# RCboat.net
KiCad netlist of a schematic drawn in EAGLE
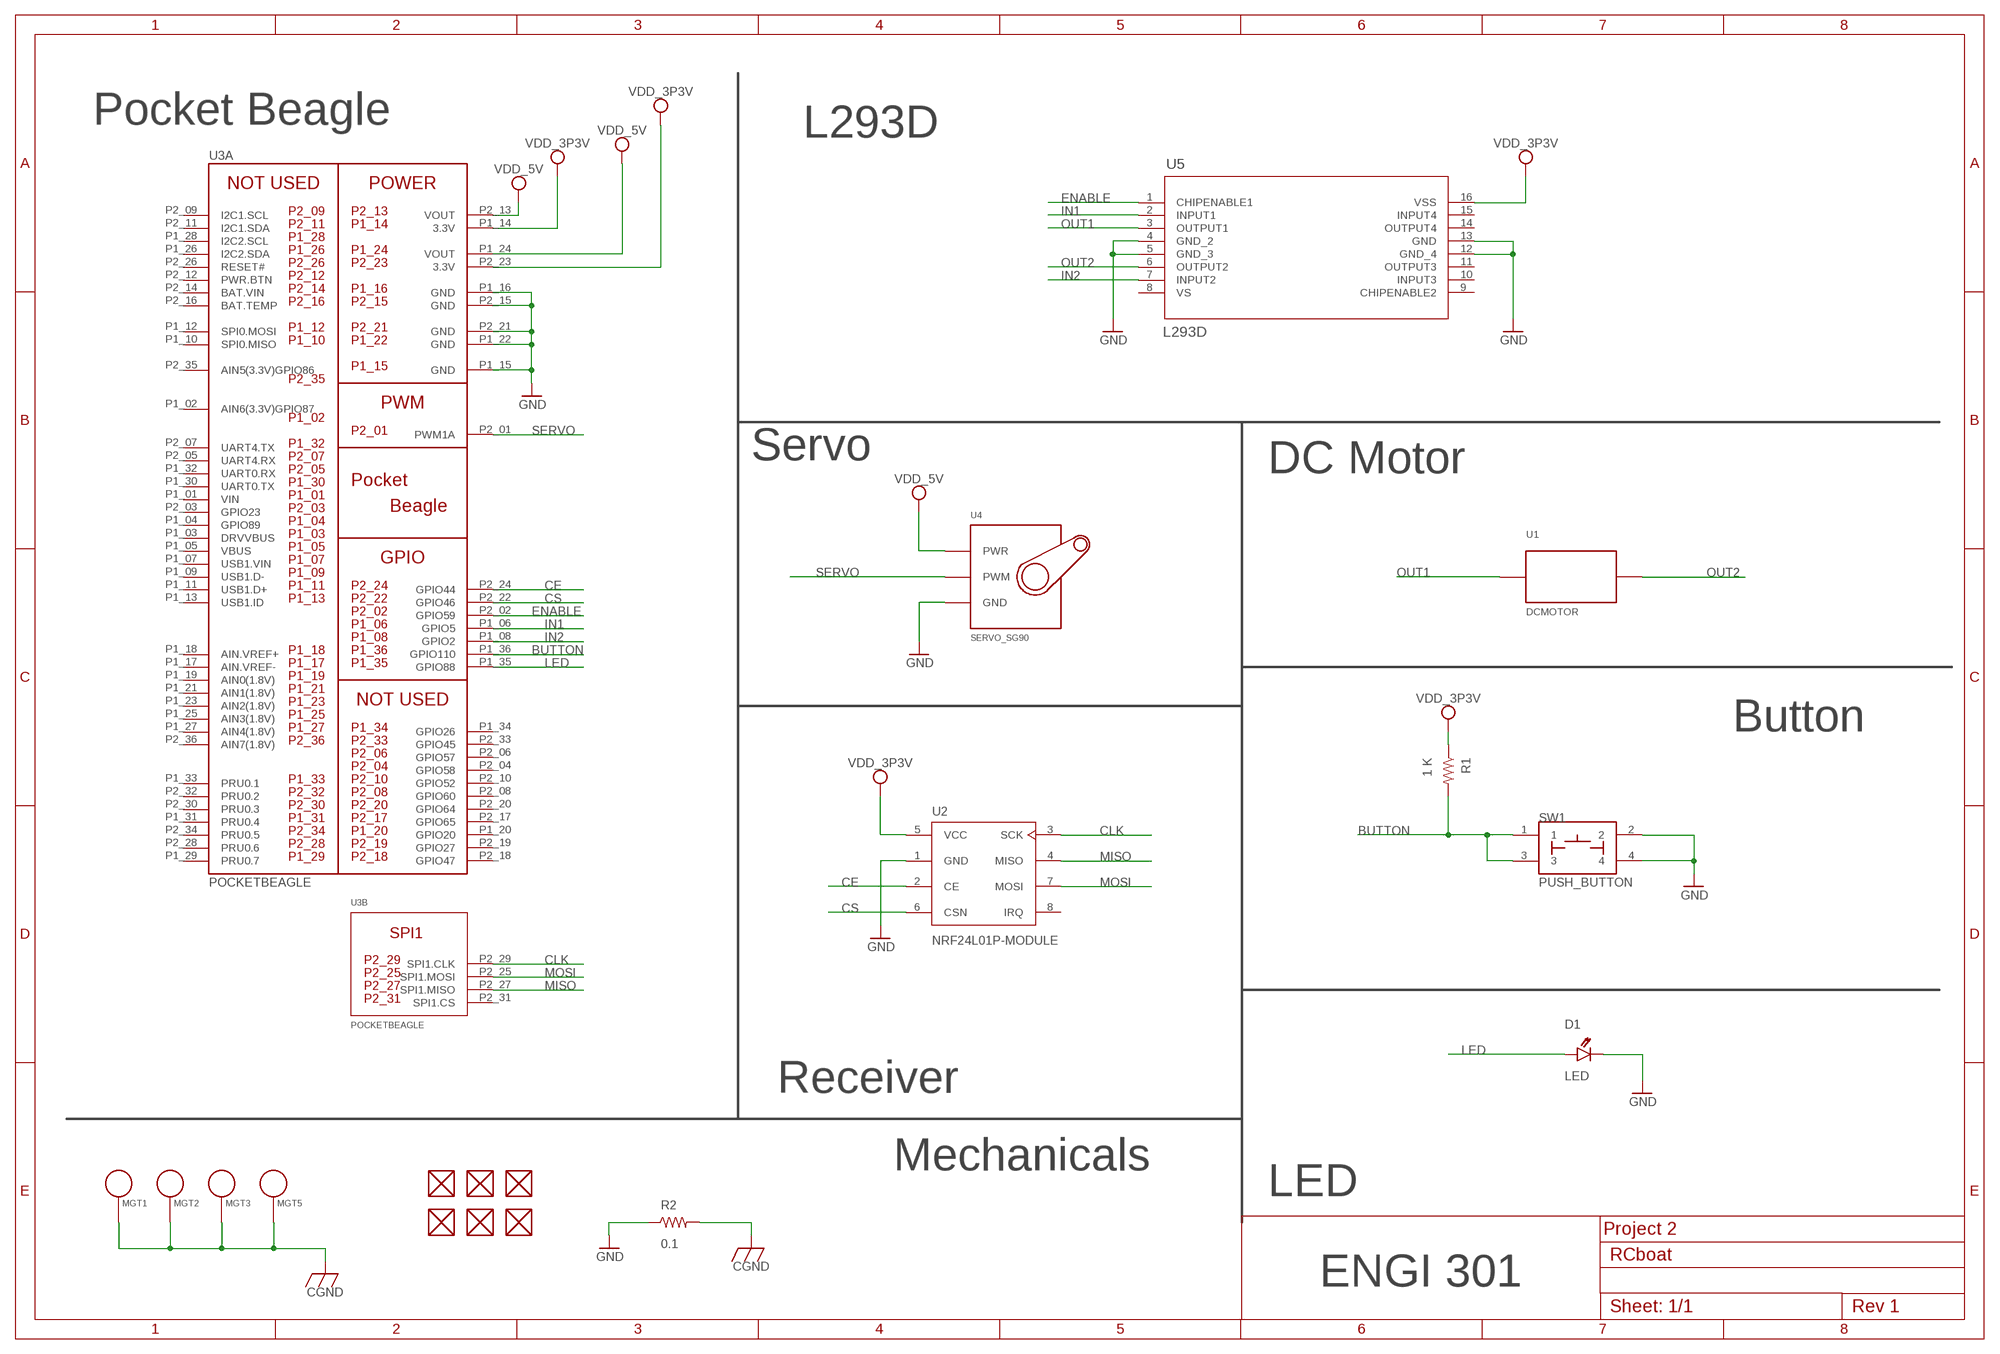
[diagram p0: schematic, sheet 1]

(export (version "E")
  (design (tool "Eeschema 10.0.6"))
  (components
    (comp (ref "D1")
      (value "LED")
      (footprint "eagle-import:EIA-STD")
      (libsource (lib "eagle-import") (part "LED"))
    )
    (comp (ref "FUD1")
      (value "FIDUCIAL")
      (footprint "eagle-import:FIDUCIAL_40MIL")
      (libsource (lib "eagle-import") (part "FIDUCIAL"))
    )
    (comp (ref "FUD2")
      (value "FIDUCIAL")
      (footprint "eagle-import:FIDUCIAL_40MIL")
      (libsource (lib "eagle-import") (part "FIDUCIAL"))
    )
    (comp (ref "FUD3")
      (value "FIDUCIAL")
      (footprint "eagle-import:FIDUCIAL_40MIL")
      (libsource (lib "eagle-import") (part "FIDUCIAL"))
    )
    (comp (ref "FUD4")
      (value "FIDUCIAL")
      (footprint "eagle-import:FIDUCIAL_40MIL")
      (libsource (lib "eagle-import") (part "FIDUCIAL"))
    )
    (comp (ref "FUD5")
      (value "FIDUCIAL")
      (footprint "eagle-import:FIDUCIAL_40MIL")
      (libsource (lib "eagle-import") (part "FIDUCIAL"))
    )
    (comp (ref "FUD6")
      (value "FIDUCIAL")
      (footprint "eagle-import:FIDUCIAL_40MIL")
      (libsource (lib "eagle-import") (part "FIDUCIAL"))
    )
    (comp (ref "MGT1")
      (value "MOUNTING_HOLE")
      (footprint "eagle-import:MOUNTING_HOLE")
      (libsource (lib "eagle-import") (part "MOUNTING_HOLE"))
    )
    (comp (ref "MGT2")
      (value "MOUNTING_HOLE")
      (footprint "eagle-import:MOUNTING_HOLE")
      (libsource (lib "eagle-import") (part "MOUNTING_HOLE"))
    )
    (comp (ref "MGT3")
      (value "MOUNTING_HOLE")
      (footprint "eagle-import:MOUNTING_HOLE")
      (libsource (lib "eagle-import") (part "MOUNTING_HOLE"))
    )
    (comp (ref "MGT5")
      (value "MOUNTING_HOLE")
      (footprint "eagle-import:MOUNTING_HOLE")
      (libsource (lib "eagle-import") (part "MOUNTING_HOLE"))
    )
    (comp (ref "R1")
      (value "1 K")
      (footprint "eagle-import:R0603")
      (libsource (lib "eagle-import") (part "R_R0603"))
    )
    (comp (ref "R2")
      (value "0.1")
      (footprint "eagle-import:R0805")
      (libsource (lib "eagle-import") (part "R_R0805"))
    )
    (comp (ref "SW1")
      (value "PUSH_BUTTON")
      (footprint "eagle-import:BUTTON_12.5MM")
      (libsource (lib "eagle-import") (part "PUSH_BUTTON"))
    )
    (comp (ref "U1")
      (value "DCMOTOR")
      (footprint "eagle-import:DCMOTOR")
      (libsource (lib "eagle-import") (part "DCMOTOR"))
    )
    (comp (ref "U2")
      (value "NRF24L01P-MODULE")
      (footprint "eagle-import:NRF24L01P-MODULE")
      (libsource (lib "eagle-import") (part "NRF24L01P-MODULE"))
    )
    (comp (ref "U3")
      (value "POCKETBEAGLE")
      (footprint "eagle-import:POCKETBEAGLE")
      (libsource (lib "eagle-import") (part "POCKETBEAGLE"))
    )
    (comp (ref "U4")
      (value "SERVO_SG90")
      (footprint "eagle-import:SERVO-X1")
      (libsource (lib "eagle-import") (part "SERVO_SG90"))
    )
    (comp (ref "U5")
      (value "L293D")
      (footprint "eagle-import:POWERDIP-16_STM")
      (fields (field (name "COPYRIGHT") "Copyright (C) 2021 Ultra Librarian. All rights reserved."))
      (libsource (lib "eagle-import") (part "L293D"))
    )
  )
  (nets
    (net (code "1") (name "/BAT.VIN") (class "Default")
      (node (ref "U3") (pin "P2_14") (pinfunction "BAT.VIN_P2_14") (pintype "power_in"))
    )
    (net (code "2") (name "/BUTTON") (class "Default")
      (node (ref "R1") (pin "2") (pinfunction "2_2") (pintype "passive"))
      (node (ref "SW1") (pin "1") (pinfunction "1_1") (pintype "bidirectional"))
      (node (ref "SW1") (pin "3") (pinfunction "3_3") (pintype "bidirectional"))
      (node (ref "U3") (pin "P1_36") (pinfunction "GPIO110_P1_36") (pintype "bidirectional"))
    )
    (net (code "3") (name "/CE") (class "Default")
      (node (ref "U2") (pin "2") (pinfunction "CE_2") (pintype "input"))
      (node (ref "U3") (pin "P2_24") (pinfunction "GPIO44_P2_24") (pintype "bidirectional"))
    )
    (net (code "4") (name "/CLK") (class "Default")
      (node (ref "U2") (pin "3") (pinfunction "SCK_3") (pintype "input"))
      (node (ref "U3") (pin "P2_29") (pinfunction "SPI1.CLK_P2_29") (pintype "bidirectional"))
    )
    (net (code "5") (name "/CS") (class "Default")
      (node (ref "U2") (pin "6") (pinfunction "CSN_6") (pintype "input"))
      (node (ref "U3") (pin "P2_22") (pinfunction "GPIO46_P2_22") (pintype "bidirectional"))
    )
    (net (code "6") (name "/ENABLE") (class "Default")
      (node (ref "U3") (pin "P2_02") (pinfunction "GPIO59_P2_02") (pintype "bidirectional"))
      (node (ref "U5") (pin "1") (pinfunction "CHIPENABLE1_1") (pintype "output"))
    )
    (net (code "7") (name "/IN1") (class "Default")
      (node (ref "U3") (pin "P1_06") (pinfunction "GPIO5_P1_06") (pintype "bidirectional"))
      (node (ref "U5") (pin "2") (pinfunction "INPUT1_2") (pintype "input"))
    )
    (net (code "8") (name "/IN2") (class "Default")
      (node (ref "U3") (pin "P1_08") (pinfunction "GPIO2_P1_08") (pintype "bidirectional"))
      (node (ref "U5") (pin "7") (pinfunction "INPUT2_7") (pintype "input"))
    )
    (net (code "9") (name "/LED") (class "Default")
      (node (ref "D1") (pin "ANODE") (pinfunction "ANODE_ANODE") (pintype "bidirectional"))
      (node (ref "U3") (pin "P1_35") (pinfunction "GPIO88_P1_35") (pintype "bidirectional"))
    )
    (net (code "10") (name "/MISO") (class "Default")
      (node (ref "U2") (pin "4") (pinfunction "MISO_4") (pintype "input"))
      (node (ref "U3") (pin "P2_27") (pinfunction "SPI1.MISO_P2_27") (pintype "bidirectional"))
    )
    (net (code "11") (name "/MOSI") (class "Default")
      (node (ref "U2") (pin "7") (pinfunction "MOSI_7") (pintype "input"))
      (node (ref "U3") (pin "P2_25") (pinfunction "SPI1.MOSI_P2_25") (pintype "bidirectional"))
    )
    (net (code "12") (name "/OUT1") (class "Default")
      (node (ref "U1") (pin "1") (pinfunction "V1_1") (pintype "power_in"))
      (node (ref "U5") (pin "3") (pinfunction "OUTPUT1_3") (pintype "output"))
    )
    (net (code "13") (name "/OUT2") (class "Default")
      (node (ref "U1") (pin "2") (pinfunction "2_2") (pintype "power_in"))
      (node (ref "U5") (pin "6") (pinfunction "OUTPUT2_6") (pintype "output"))
    )
    (net (code "14") (name "/SERVO") (class "Default")
      (node (ref "U3") (pin "P2_01") (pinfunction "PWM1A_P2_01") (pintype "bidirectional"))
      (node (ref "U4") (pin "SIG") (pinfunction "PWM_SIG") (pintype "bidirectional"))
    )
    (net (code "15") (name "/VIN") (class "Default")
      (node (ref "U3") (pin "P1_01") (pinfunction "VIN_P1_01") (pintype "power_in"))
    )
    (net (code "16") (name "/VS") (class "Default")
      (node (ref "U5") (pin "8") (pinfunction "VS_8") (pintype "power_in"))
    )
    (net (code "17") (name "CGND") (class "Default")
      (node (ref "MGT1") (pin "P$1") (pinfunction "P$1_P$1") (pintype "bidirectional"))
      (node (ref "MGT2") (pin "P$1") (pinfunction "P$1_P$1") (pintype "bidirectional"))
      (node (ref "MGT3") (pin "P$1") (pinfunction "P$1_P$1") (pintype "bidirectional"))
      (node (ref "MGT5") (pin "P$1") (pinfunction "P$1_P$1") (pintype "bidirectional"))
      (node (ref "R2") (pin "2") (pinfunction "2_2") (pintype "passive"))
    )
    (net (code "18") (name "GND") (class "Default")
      (node (ref "D1") (pin "CATHODE") (pinfunction "CATHODE_CATHODE") (pintype "bidirectional"))
      (node (ref "R2") (pin "1") (pinfunction "1_1") (pintype "passive"))
      (node (ref "SW1") (pin "2") (pinfunction "2_2") (pintype "bidirectional"))
      (node (ref "SW1") (pin "4") (pinfunction "4_4") (pintype "bidirectional"))
      (node (ref "U2") (pin "1") (pinfunction "GND_1") (pintype "power_in"))
      (node (ref "U3") (pin "P1_15") (pinfunction "GND_P1_15") (pintype "bidirectional"))
      (node (ref "U3") (pin "P1_16") (pinfunction "GND_P1_16") (pintype "power_in"))
      (node (ref "U3") (pin "P1_22") (pinfunction "GND_P1_22") (pintype "power_in"))
      (node (ref "U3") (pin "P2_15") (pinfunction "GND_P2_15") (pintype "power_in"))
      (node (ref "U3") (pin "P2_21") (pinfunction "GND_P2_21") (pintype "power_in"))
      (node (ref "U4") (pin "GND") (pinfunction "GND_GND") (pintype "bidirectional"))
      (node (ref "U5") (pin "12") (pinfunction "GND_4_12") (pintype "passive"))
      (node (ref "U5") (pin "13") (pinfunction "GND_13") (pintype "passive"))
      (node (ref "U5") (pin "4") (pinfunction "GND_2_4") (pintype "passive"))
      (node (ref "U5") (pin "5") (pinfunction "GND_3_5") (pintype "passive"))
    )
    (net (code "19") (name "VDD_3P3V") (class "Default")
      (node (ref "R1") (pin "1") (pinfunction "1_1") (pintype "passive"))
      (node (ref "U2") (pin "5") (pinfunction "VCC_5") (pintype "power_in"))
      (node (ref "U3") (pin "P1_14") (pinfunction "3.3V_P1_14") (pintype "power_in"))
      (node (ref "U3") (pin "P2_23") (pinfunction "3.3V_P2_23") (pintype "power_in"))
      (node (ref "U5") (pin "16") (pinfunction "VSS_16") (pintype "power_in"))
    )
    (net (code "20") (name "VDD_5V") (class "Default")
      (node (ref "U3") (pin "P1_24") (pinfunction "VOUT_P1_24") (pintype "power_in"))
      (node (ref "U3") (pin "P2_13") (pinfunction "VOUT_P2_13") (pintype "power_in"))
      (node (ref "U4") (pin "PWR") (pinfunction "PWR_PWR") (pintype "bidirectional"))
    )
    (net (code "21") (name "unconnected-(FUD1-PadP$1)") (class "Default")
      (node (ref "FUD1") (pin "P$1") (pinfunction "P$1_P$1") (pintype "no_connect"))
    )
    (net (code "22") (name "unconnected-(FUD2-PadP$1)") (class "Default")
      (node (ref "FUD2") (pin "P$1") (pinfunction "P$1_P$1") (pintype "no_connect"))
    )
    (net (code "23") (name "unconnected-(FUD3-PadP$1)") (class "Default")
      (node (ref "FUD3") (pin "P$1") (pinfunction "P$1_P$1") (pintype "no_connect"))
    )
    (net (code "24") (name "unconnected-(FUD4-PadP$1)") (class "Default")
      (node (ref "FUD4") (pin "P$1") (pinfunction "P$1_P$1") (pintype "no_connect"))
    )
    (net (code "25") (name "unconnected-(FUD5-PadP$1)") (class "Default")
      (node (ref "FUD5") (pin "P$1") (pinfunction "P$1_P$1") (pintype "no_connect"))
    )
    (net (code "26") (name "unconnected-(FUD6-PadP$1)") (class "Default")
      (node (ref "FUD6") (pin "P$1") (pinfunction "P$1_P$1") (pintype "no_connect"))
    )
    (net (code "27") (name "unconnected-(U2-IRQ-Pad8)") (class "Default")
      (node (ref "U2") (pin "8") (pinfunction "IRQ_8") (pintype "input"))
    )
    (net (code "28") (name "unconnected-(U3A-AIN.VREF+-PadP1_18)") (class "Default")
      (node (ref "U3") (pin "P1_18") (pinfunction "AIN.VREF+_P1_18") (pintype "input"))
    )
    (net (code "29") (name "unconnected-(U3A-AIN.VREF--PadP1_17)") (class "Default")
      (node (ref "U3") (pin "P1_17") (pinfunction "AIN.VREF-_P1_17") (pintype "input"))
    )
    (net (code "30") (name "unconnected-(U3A-AIN0(1.8V)-PadP1_19)") (class "Default")
      (node (ref "U3") (pin "P1_19") (pinfunction "AIN0(1.8V)_P1_19") (pintype "input"))
    )
    (net (code "31") (name "unconnected-(U3A-AIN1(1.8V)-PadP1_21)") (class "Default")
      (node (ref "U3") (pin "P1_21") (pinfunction "AIN1(1.8V)_P1_21") (pintype "input"))
    )
    (net (code "32") (name "unconnected-(U3A-AIN2(1.8V)-PadP1_23)") (class "Default")
      (node (ref "U3") (pin "P1_23") (pinfunction "AIN2(1.8V)_P1_23") (pintype "input"))
    )
    (net (code "33") (name "unconnected-(U3A-AIN3(1.8V)-PadP1_25)") (class "Default")
      (node (ref "U3") (pin "P1_25") (pinfunction "AIN3(1.8V)_P1_25") (pintype "input"))
    )
    (net (code "34") (name "unconnected-(U3A-AIN4(1.8V)-PadP1_27)") (class "Default")
      (node (ref "U3") (pin "P1_27") (pinfunction "AIN4(1.8V)_P1_27") (pintype "input"))
    )
    (net (code "35") (name "unconnected-(U3A-AIN5(3.3V)GPIO86-PadP2_35)") (class "Default")
      (node (ref "U3") (pin "P2_35") (pinfunction "AIN5(3.3V)GPIO86_P2_35") (pintype "bidirectional"))
    )
    (net (code "36") (name "unconnected-(U3A-AIN6(3.3V)GPIO87-PadP1_02)") (class "Default")
      (node (ref "U3") (pin "P1_02") (pinfunction "AIN6(3.3V)GPIO87_P1_02") (pintype "bidirectional"))
    )
    (net (code "37") (name "unconnected-(U3A-AIN7(1.8V)-PadP2_36)") (class "Default")
      (node (ref "U3") (pin "P2_36") (pinfunction "AIN7(1.8V)_P2_36") (pintype "input"))
    )
    (net (code "38") (name "unconnected-(U3A-BAT.TEMP-PadP2_16)") (class "Default")
      (node (ref "U3") (pin "P2_16") (pinfunction "BAT.TEMP_P2_16") (pintype "input"))
    )
    (net (code "39") (name "unconnected-(U3A-DRVVBUS-PadP1_03)") (class "Default")
      (node (ref "U3") (pin "P1_03") (pinfunction "DRVVBUS_P1_03") (pintype "bidirectional"))
    )
    (net (code "40") (name "unconnected-(U3A-GPIO20-PadP1_20)") (class "Default")
      (node (ref "U3") (pin "P1_20") (pinfunction "GPIO20_P1_20") (pintype "bidirectional"))
    )
    (net (code "41") (name "unconnected-(U3A-GPIO23-PadP2_03)") (class "Default")
      (node (ref "U3") (pin "P2_03") (pinfunction "GPIO23_P2_03") (pintype "bidirectional"))
    )
    (net (code "42") (name "unconnected-(U3A-GPIO26-PadP1_34)") (class "Default")
      (node (ref "U3") (pin "P1_34") (pinfunction "GPIO26_P1_34") (pintype "bidirectional"))
    )
    (net (code "43") (name "unconnected-(U3A-GPIO27-PadP2_19)") (class "Default")
      (node (ref "U3") (pin "P2_19") (pinfunction "GPIO27_P2_19") (pintype "bidirectional"))
    )
    (net (code "44") (name "unconnected-(U3A-GPIO45-PadP2_33)") (class "Default")
      (node (ref "U3") (pin "P2_33") (pinfunction "GPIO45_P2_33") (pintype "bidirectional"))
    )
    (net (code "45") (name "unconnected-(U3A-GPIO47-PadP2_18)") (class "Default")
      (node (ref "U3") (pin "P2_18") (pinfunction "GPIO47_P2_18") (pintype "bidirectional"))
    )
    (net (code "46") (name "unconnected-(U3A-GPIO52-PadP2_10)") (class "Default")
      (node (ref "U3") (pin "P2_10") (pinfunction "GPIO52_P2_10") (pintype "bidirectional"))
    )
    (net (code "47") (name "unconnected-(U3A-GPIO57-PadP2_06)") (class "Default")
      (node (ref "U3") (pin "P2_06") (pinfunction "GPIO57_P2_06") (pintype "bidirectional"))
    )
    (net (code "48") (name "unconnected-(U3A-GPIO58-PadP2_04)") (class "Default")
      (node (ref "U3") (pin "P2_04") (pinfunction "GPIO58_P2_04") (pintype "bidirectional"))
    )
    (net (code "49") (name "unconnected-(U3A-GPIO60-PadP2_08)") (class "Default")
      (node (ref "U3") (pin "P2_08") (pinfunction "GPIO60_P2_08") (pintype "bidirectional"))
    )
    (net (code "50") (name "unconnected-(U3A-GPIO64-PadP2_20)") (class "Default")
      (node (ref "U3") (pin "P2_20") (pinfunction "GPIO64_P2_20") (pintype "bidirectional"))
    )
    (net (code "51") (name "unconnected-(U3A-GPIO65-PadP2_17)") (class "Default")
      (node (ref "U3") (pin "P2_17") (pinfunction "GPIO65_P2_17") (pintype "bidirectional"))
    )
    (net (code "52") (name "unconnected-(U3A-GPIO89-PadP1_04)") (class "Default")
      (node (ref "U3") (pin "P1_04") (pinfunction "GPIO89_P1_04") (pintype "bidirectional"))
    )
    (net (code "53") (name "unconnected-(U3A-I2C1.SCL-PadP2_09)") (class "Default")
      (node (ref "U3") (pin "P2_09") (pinfunction "I2C1.SCL_P2_09") (pintype "bidirectional"))
    )
    (net (code "54") (name "unconnected-(U3A-I2C1.SDA-PadP2_11)") (class "Default")
      (node (ref "U3") (pin "P2_11") (pinfunction "I2C1.SDA_P2_11") (pintype "bidirectional"))
    )
    (net (code "55") (name "unconnected-(U3A-I2C2.SCL-PadP1_28)") (class "Default")
      (node (ref "U3") (pin "P1_28") (pinfunction "I2C2.SCL_P1_28") (pintype "bidirectional"))
    )
    (net (code "56") (name "unconnected-(U3A-I2C2.SDA-PadP1_26)") (class "Default")
      (node (ref "U3") (pin "P1_26") (pinfunction "I2C2.SDA_P1_26") (pintype "bidirectional"))
    )
    (net (code "57") (name "unconnected-(U3A-PRU0.1-PadP1_33)") (class "Default")
      (node (ref "U3") (pin "P1_33") (pinfunction "PRU0.1_P1_33") (pintype "bidirectional"))
    )
    (net (code "58") (name "unconnected-(U3A-PRU0.2-PadP2_32)") (class "Default")
      (node (ref "U3") (pin "P2_32") (pinfunction "PRU0.2_P2_32") (pintype "bidirectional"))
    )
    (net (code "59") (name "unconnected-(U3A-PRU0.3-PadP2_30)") (class "Default")
      (node (ref "U3") (pin "P2_30") (pinfunction "PRU0.3_P2_30") (pintype "bidirectional"))
    )
    (net (code "60") (name "unconnected-(U3A-PRU0.4-PadP1_31)") (class "Default")
      (node (ref "U3") (pin "P1_31") (pinfunction "PRU0.4_P1_31") (pintype "bidirectional"))
    )
    (net (code "61") (name "unconnected-(U3A-PRU0.5-PadP2_34)") (class "Default")
      (node (ref "U3") (pin "P2_34") (pinfunction "PRU0.5_P2_34") (pintype "bidirectional"))
    )
    (net (code "62") (name "unconnected-(U3A-PRU0.6-PadP2_28)") (class "Default")
      (node (ref "U3") (pin "P2_28") (pinfunction "PRU0.6_P2_28") (pintype "bidirectional"))
    )
    (net (code "63") (name "unconnected-(U3A-PRU0.7-PadP1_29)") (class "Default")
      (node (ref "U3") (pin "P1_29") (pinfunction "PRU0.7_P1_29") (pintype "bidirectional"))
    )
    (net (code "64") (name "unconnected-(U3A-PWR.BTN-PadP2_12)") (class "Default")
      (node (ref "U3") (pin "P2_12") (pinfunction "PWR.BTN_P2_12") (pintype "input"))
    )
    (net (code "65") (name "unconnected-(U3A-RESET#-PadP2_26)") (class "Default")
      (node (ref "U3") (pin "P2_26") (pinfunction "RESET#_P2_26") (pintype "input"))
    )
    (net (code "66") (name "unconnected-(U3A-SPI0.MISO-PadP1_10)") (class "Default")
      (node (ref "U3") (pin "P1_10") (pinfunction "SPI0.MISO_P1_10") (pintype "bidirectional"))
    )
    (net (code "67") (name "unconnected-(U3A-SPI0.MOSI-PadP1_12)") (class "Default")
      (node (ref "U3") (pin "P1_12") (pinfunction "SPI0.MOSI_P1_12") (pintype "bidirectional"))
    )
    (net (code "68") (name "unconnected-(U3A-UART0.RX-PadP1_32)") (class "Default")
      (node (ref "U3") (pin "P1_32") (pinfunction "UART0.RX_P1_32") (pintype "bidirectional"))
    )
    (net (code "69") (name "unconnected-(U3A-UART0.TX-PadP1_30)") (class "Default")
      (node (ref "U3") (pin "P1_30") (pinfunction "UART0.TX_P1_30") (pintype "bidirectional"))
    )
    (net (code "70") (name "unconnected-(U3A-UART4.RX-PadP2_05)") (class "Default")
      (node (ref "U3") (pin "P2_05") (pinfunction "UART4.RX_P2_05") (pintype "bidirectional"))
    )
    (net (code "71") (name "unconnected-(U3A-UART4.TX-PadP2_07)") (class "Default")
      (node (ref "U3") (pin "P2_07") (pinfunction "UART4.TX_P2_07") (pintype "bidirectional"))
    )
    (net (code "72") (name "unconnected-(U3A-USB1.D+-PadP1_11)") (class "Default")
      (node (ref "U3") (pin "P1_11") (pinfunction "USB1.D+_P1_11") (pintype "bidirectional"))
    )
    (net (code "73") (name "unconnected-(U3A-USB1.D--PadP1_09)") (class "Default")
      (node (ref "U3") (pin "P1_09") (pinfunction "USB1.D-_P1_09") (pintype "bidirectional"))
    )
    (net (code "74") (name "unconnected-(U3A-USB1.ID-PadP1_13)") (class "Default")
      (node (ref "U3") (pin "P1_13") (pinfunction "USB1.ID_P1_13") (pintype "bidirectional"))
    )
    (net (code "75") (name "unconnected-(U3A-USB1.VIN-PadP1_07)") (class "Default")
      (node (ref "U3") (pin "P1_07") (pinfunction "USB1.VIN_P1_07") (pintype "bidirectional"))
    )
    (net (code "76") (name "unconnected-(U3A-VBUS-PadP1_05)") (class "Default")
      (node (ref "U3") (pin "P1_05") (pinfunction "VBUS_P1_05") (pintype "bidirectional"))
    )
    (net (code "77") (name "unconnected-(U3B-SPI1.CS-PadP2_31)") (class "Default")
      (node (ref "U3") (pin "P2_31") (pinfunction "SPI1.CS_P2_31") (pintype "bidirectional"))
    )
    (net (code "78") (name "unconnected-(U5-CHIPENABLE2-Pad9)") (class "Default")
      (node (ref "U5") (pin "9") (pinfunction "CHIPENABLE2_9") (pintype "output"))
    )
    (net (code "79") (name "unconnected-(U5-INPUT3-Pad10)") (class "Default")
      (node (ref "U5") (pin "10") (pinfunction "INPUT3_10") (pintype "input"))
    )
    (net (code "80") (name "unconnected-(U5-INPUT4-Pad15)") (class "Default")
      (node (ref "U5") (pin "15") (pinfunction "INPUT4_15") (pintype "input"))
    )
    (net (code "81") (name "unconnected-(U5-OUTPUT3-Pad11)") (class "Default")
      (node (ref "U5") (pin "11") (pinfunction "OUTPUT3_11") (pintype "output"))
    )
    (net (code "82") (name "unconnected-(U5-OUTPUT4-Pad14)") (class "Default")
      (node (ref "U5") (pin "14") (pinfunction "OUTPUT4_14") (pintype "output"))
    )
  )
)
